# untitled.net
KiCad netlist of a schematic drawn in EAGLE
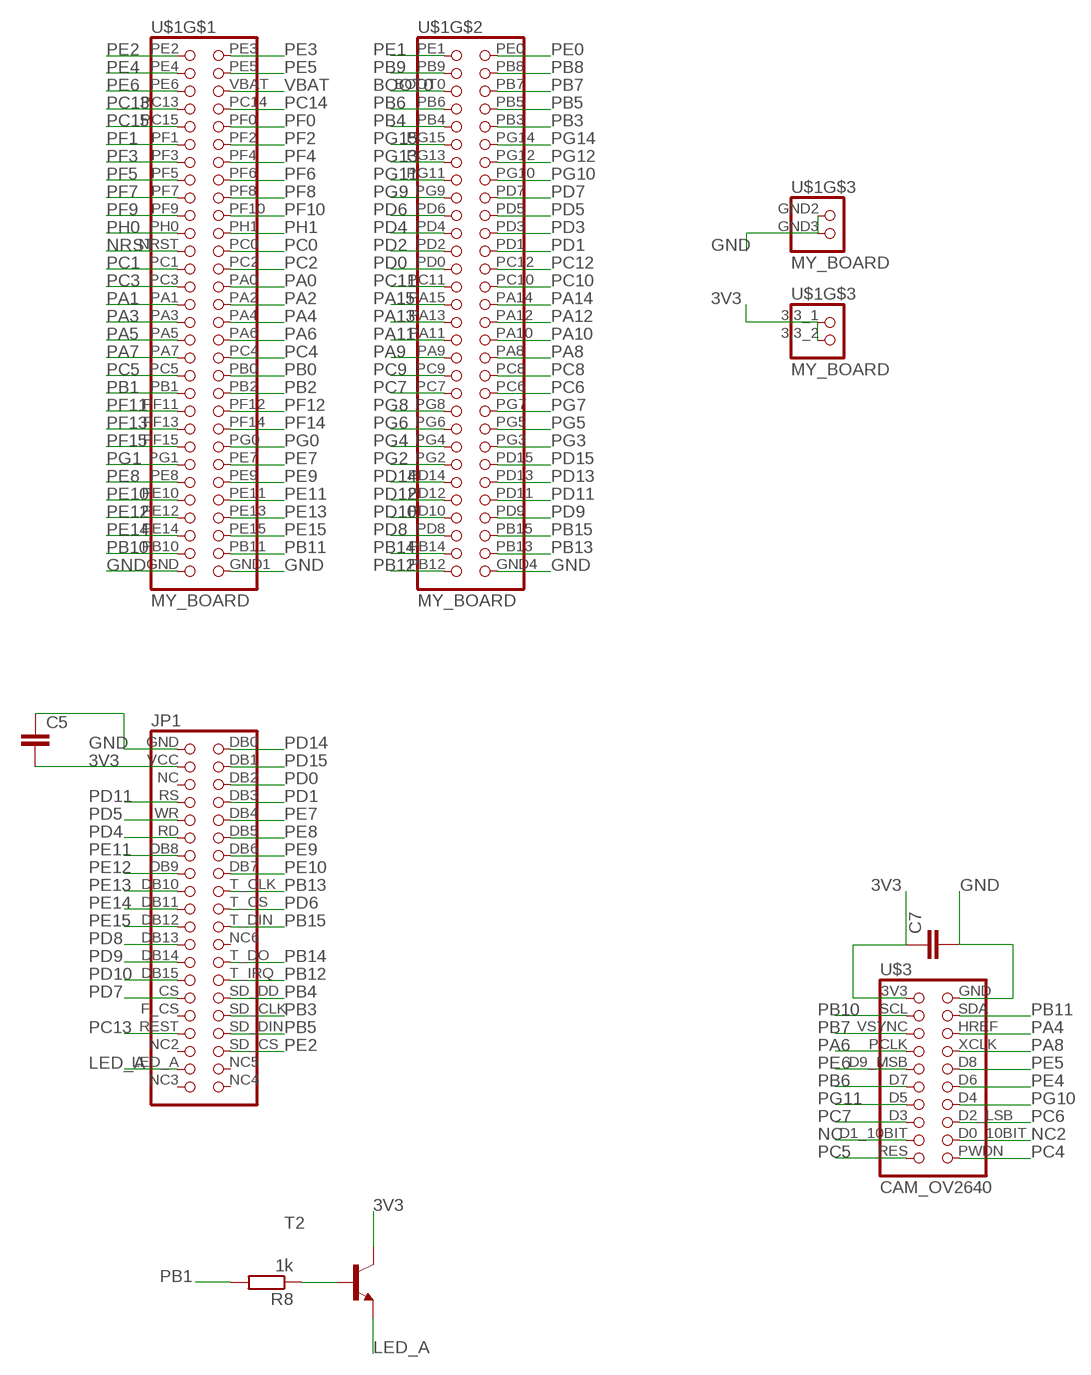
[diagram p0: schematic, sheet 1]

(export (version "E")
  (design (tool "Eeschema 10.0.6"))
  (components
    (comp (ref "C5")
      (value "C-EUC1206")
      (footprint "eagle-import:C1206")
      (libsource (lib "eagle-import") (part "C-EUC1206"))
    )
    (comp (ref "C7")
      (value "C-EUC1206")
      (footprint "eagle-import:C1206")
      (libsource (lib "eagle-import") (part "C-EUC1206"))
    )
    (comp (ref "JP1")
      (value "LCD320QVBLCD320QVB")
      (footprint "eagle-import:2X20")
      (libsource (lib "eagle-import") (part "LCD320QVBLCD320QVB"))
    )
    (comp (ref "R8")
      (value "1k")
      (footprint "eagle-import:R1206")
      (libsource (lib "eagle-import") (part "R-EU_R1206"))
    )
    (comp (ref "T2")
      (value "BC817-16-NPN-SOT23-BEC")
      (footprint "eagle-import:SOT23-BEC")
      (libsource (lib "eagle-import") (part "-NPN-SOT23-BECBC817-16"))
    )
    (comp (ref "U$1")
      (value "MY_BOARD")
      (footprint "eagle-import:MY_BOARD")
      (libsource (lib "eagle-import") (part "MY_BOARD"))
    )
    (comp (ref "U$3")
      (value "CAM_OV2640")
      (footprint "eagle-import:CAM_OV2640")
      (libsource (lib "eagle-import") (part "CAM_OV2640"))
    )
  )
  (nets
    (net (code "1") (name "/3V3") (class "Default")
      (node (ref "C5") (pin "2") (pinfunction "2_2") (pintype "passive"))
      (node (ref "C7") (pin "1") (pinfunction "1_1") (pintype "passive"))
      (node (ref "JP1") (pin "VCC") (pinfunction "3_VCC") (pintype "passive"))
      (node (ref "T2") (pin "C") (pinfunction "C_C") (pintype "passive"))
      (node (ref "U$1") (pin "3,3_1") (pinfunction "1_3,3_1") (pintype "passive"))
      (node (ref "U$1") (pin "3,3_2") (pinfunction "2_3,3_2") (pintype "passive"))
      (node (ref "U$3") (pin "3V3") (pinfunction "3V3_3V3") (pintype "passive"))
    )
    (net (code "2") (name "/BOOT0") (class "Default")
      (node (ref "U$1") (pin "BOOT0") (pinfunction "5_BOOT0") (pintype "passive"))
    )
    (net (code "3") (name "/GND") (class "Default")
      (node (ref "C5") (pin "1") (pinfunction "1_1") (pintype "passive"))
      (node (ref "C7") (pin "2") (pinfunction "2_2") (pintype "passive"))
      (node (ref "JP1") (pin "GND") (pinfunction "1_GND") (pintype "passive"))
      (node (ref "U$1") (pin "GND") (pinfunction "59_GND") (pintype "passive"))
      (node (ref "U$1") (pin "GND1") (pinfunction "60_GND1") (pintype "passive"))
      (node (ref "U$1") (pin "GND2") (pinfunction "3_GND2") (pintype "passive"))
      (node (ref "U$1") (pin "GND3") (pinfunction "4_GND3") (pintype "passive"))
      (node (ref "U$1") (pin "GND4") (pinfunction "60_GND4") (pintype "passive"))
      (node (ref "U$3") (pin "GND") (pinfunction "GND_GND") (pintype "passive"))
    )
    (net (code "4") (name "/LED_A") (class "Default")
      (node (ref "JP1") (pin "LED_A") (pinfunction "37_LED_A") (pintype "passive"))
      (node (ref "T2") (pin "E") (pinfunction "E_E") (pintype "passive"))
    )
    (net (code "5") (name "/NC") (class "Default")
      (node (ref "U$3") (pin "D1_10BIT") (pinfunction "D1_10BIT_D1_10BIT") (pintype "passive"))
    )
    (net (code "6") (name "/NC2") (class "Default")
      (node (ref "U$3") (pin "D0_10BIT") (pinfunction "D0_10BIT_D0_10BIT") (pintype "passive"))
    )
    (net (code "7") (name "/NRST") (class "Default")
      (node (ref "U$1") (pin "NRST") (pinfunction "23_NRST") (pintype "passive"))
    )
    (net (code "8") (name "/PA0") (class "Default")
      (node (ref "U$1") (pin "PA0") (pinfunction "28_PA0") (pintype "passive"))
    )
    (net (code "9") (name "/PA1") (class "Default")
      (node (ref "U$1") (pin "PA1") (pinfunction "29_PA1") (pintype "passive"))
    )
    (net (code "10") (name "/PA2") (class "Default")
      (node (ref "U$1") (pin "PA2") (pinfunction "30_PA2") (pintype "passive"))
    )
    (net (code "11") (name "/PA3") (class "Default")
      (node (ref "U$1") (pin "PA3") (pinfunction "31_PA3") (pintype "passive"))
    )
    (net (code "12") (name "/PA4") (class "Default")
      (node (ref "U$1") (pin "PA4") (pinfunction "32_PA4") (pintype "passive"))
      (node (ref "U$3") (pin "HREF") (pinfunction "HREF_HREF") (pintype "passive"))
    )
    (net (code "13") (name "/PA5") (class "Default")
      (node (ref "U$1") (pin "PA5") (pinfunction "33_PA5") (pintype "passive"))
    )
    (net (code "14") (name "/PA6") (class "Default")
      (node (ref "U$1") (pin "PA6") (pinfunction "34_PA6") (pintype "passive"))
      (node (ref "U$3") (pin "PCLK") (pinfunction "PCLK_PCLK") (pintype "passive"))
    )
    (net (code "15") (name "/PA7") (class "Default")
      (node (ref "U$1") (pin "PA7") (pinfunction "35_PA7") (pintype "passive"))
    )
    (net (code "16") (name "/PA8") (class "Default")
      (node (ref "U$1") (pin "PA8") (pinfunction "36_PA8") (pintype "passive"))
      (node (ref "U$3") (pin "XCLK") (pinfunction "XCLK_XCLK") (pintype "passive"))
    )
    (net (code "17") (name "/PA9") (class "Default")
      (node (ref "U$1") (pin "PA9") (pinfunction "35_PA9") (pintype "passive"))
    )
    (net (code "18") (name "/PA10") (class "Default")
      (node (ref "U$1") (pin "PA10") (pinfunction "34_PA10") (pintype "passive"))
    )
    (net (code "19") (name "/PA11") (class "Default")
      (node (ref "U$1") (pin "PA11") (pinfunction "33_PA11") (pintype "passive"))
    )
    (net (code "20") (name "/PA12") (class "Default")
      (node (ref "U$1") (pin "PA12") (pinfunction "32_PA12") (pintype "passive"))
    )
    (net (code "21") (name "/PA13") (class "Default")
      (node (ref "U$1") (pin "PA13") (pinfunction "31_PA13") (pintype "passive"))
    )
    (net (code "22") (name "/PA14") (class "Default")
      (node (ref "U$1") (pin "PA14") (pinfunction "30_PA14") (pintype "passive"))
    )
    (net (code "23") (name "/PA15") (class "Default")
      (node (ref "U$1") (pin "PA15") (pinfunction "29_PA15") (pintype "passive"))
    )
    (net (code "24") (name "/PB0") (class "Default")
      (node (ref "U$1") (pin "PB0") (pinfunction "38_PB0") (pintype "passive"))
    )
    (net (code "25") (name "/PB1") (class "Default")
      (node (ref "R8") (pin "2") (pinfunction "2_2") (pintype "passive"))
      (node (ref "U$1") (pin "PB1") (pinfunction "39_PB1") (pintype "passive"))
    )
    (net (code "26") (name "/PB2") (class "Default")
      (node (ref "U$1") (pin "PB2") (pinfunction "40_PB2") (pintype "passive"))
    )
    (net (code "27") (name "/PB3") (class "Default")
      (node (ref "JP1") (pin "SD_CLK") (pinfunction "32_SD_CLK") (pintype "passive"))
      (node (ref "U$1") (pin "PB3") (pinfunction "10_PB3") (pintype "passive"))
    )
    (net (code "28") (name "/PB4") (class "Default")
      (node (ref "JP1") (pin "SD_DD") (pinfunction "30_SD_DD") (pintype "passive"))
      (node (ref "U$1") (pin "PB4") (pinfunction "9_PB4") (pintype "passive"))
    )
    (net (code "29") (name "/PB5") (class "Default")
      (node (ref "JP1") (pin "SD_DIN") (pinfunction "34_SD_DIN") (pintype "passive"))
      (node (ref "U$1") (pin "PB5") (pinfunction "8_PB5") (pintype "passive"))
    )
    (net (code "30") (name "/PB6") (class "Default")
      (node (ref "U$1") (pin "PB6") (pinfunction "7_PB6") (pintype "passive"))
      (node (ref "U$3") (pin "D7") (pinfunction "D7_D7") (pintype "passive"))
    )
    (net (code "31") (name "/PB7") (class "Default")
      (node (ref "U$1") (pin "PB7") (pinfunction "6_PB7") (pintype "passive"))
      (node (ref "U$3") (pin "VSYNC") (pinfunction "VSYNC_VSYNC") (pintype "passive"))
    )
    (net (code "32") (name "/PB8") (class "Default")
      (node (ref "U$1") (pin "PB8") (pinfunction "4_PB8") (pintype "passive"))
    )
    (net (code "33") (name "/PB9") (class "Default")
      (node (ref "U$1") (pin "PB9") (pinfunction "3_PB9") (pintype "passive"))
    )
    (net (code "34") (name "/PB10") (class "Default")
      (node (ref "U$1") (pin "PB10") (pinfunction "57_PB10") (pintype "passive"))
      (node (ref "U$3") (pin "SCL") (pinfunction "SCL_SCL") (pintype "passive"))
    )
    (net (code "35") (name "/PB11") (class "Default")
      (node (ref "U$1") (pin "PB11") (pinfunction "58_PB11") (pintype "passive"))
      (node (ref "U$3") (pin "SDA") (pinfunction "SDA_SDA") (pintype "passive"))
    )
    (net (code "36") (name "/PB12") (class "Default")
      (node (ref "JP1") (pin "T_IRQ") (pinfunction "28_T_IRQ") (pintype "passive"))
      (node (ref "U$1") (pin "PB12") (pinfunction "59_PB12") (pintype "passive"))
    )
    (net (code "37") (name "/PB13") (class "Default")
      (node (ref "JP1") (pin "T_CLK") (pinfunction "18_T_CLK") (pintype "passive"))
      (node (ref "U$1") (pin "PB13") (pinfunction "58_PB13") (pintype "passive"))
    )
    (net (code "38") (name "/PB14") (class "Default")
      (node (ref "JP1") (pin "T_DO") (pinfunction "26_T_DO") (pintype "passive"))
      (node (ref "U$1") (pin "PB14") (pinfunction "57_PB14") (pintype "passive"))
    )
    (net (code "39") (name "/PB15") (class "Default")
      (node (ref "JP1") (pin "T_DIN") (pinfunction "22_T_DIN") (pintype "passive"))
      (node (ref "U$1") (pin "PB15") (pinfunction "56_PB15") (pintype "passive"))
    )
    (net (code "40") (name "/PC0") (class "Default")
      (node (ref "U$1") (pin "PC0") (pinfunction "24_PC0") (pintype "passive"))
    )
    (net (code "41") (name "/PC1") (class "Default")
      (node (ref "U$1") (pin "PC1") (pinfunction "25_PC1") (pintype "passive"))
    )
    (net (code "42") (name "/PC2") (class "Default")
      (node (ref "U$1") (pin "PC2") (pinfunction "26_PC2") (pintype "passive"))
    )
    (net (code "43") (name "/PC3") (class "Default")
      (node (ref "U$1") (pin "PC3") (pinfunction "27_PC3") (pintype "passive"))
    )
    (net (code "44") (name "/PC4") (class "Default")
      (node (ref "U$1") (pin "PC4") (pinfunction "36_PC4") (pintype "passive"))
      (node (ref "U$3") (pin "PWDN") (pinfunction "PWDN_PWDN") (pintype "passive"))
    )
    (net (code "45") (name "/PC5") (class "Default")
      (node (ref "U$1") (pin "PC5") (pinfunction "37_PC5") (pintype "passive"))
      (node (ref "U$3") (pin "RES") (pinfunction "RES_RES") (pintype "passive"))
    )
    (net (code "46") (name "/PC6") (class "Default")
      (node (ref "U$1") (pin "PC6") (pinfunction "40_PC6") (pintype "passive"))
      (node (ref "U$3") (pin "D2_LSB") (pinfunction "D2_LSB_D2_LSB") (pintype "passive"))
    )
    (net (code "47") (name "/PC7") (class "Default")
      (node (ref "U$1") (pin "PC7") (pinfunction "39_PC7") (pintype "passive"))
      (node (ref "U$3") (pin "D3") (pinfunction "D3_D3") (pintype "passive"))
    )
    (net (code "48") (name "/PC8") (class "Default")
      (node (ref "U$1") (pin "PC8") (pinfunction "38_PC8") (pintype "passive"))
    )
    (net (code "49") (name "/PC9") (class "Default")
      (node (ref "U$1") (pin "PC9") (pinfunction "37_PC9") (pintype "passive"))
    )
    (net (code "50") (name "/PC10") (class "Default")
      (node (ref "U$1") (pin "PC10") (pinfunction "28_PC10") (pintype "passive"))
    )
    (net (code "51") (name "/PC11") (class "Default")
      (node (ref "U$1") (pin "PC11") (pinfunction "27_PC11") (pintype "passive"))
    )
    (net (code "52") (name "/PC12") (class "Default")
      (node (ref "U$1") (pin "PC12") (pinfunction "26_PC12") (pintype "passive"))
    )
    (net (code "53") (name "/PC13") (class "Default")
      (node (ref "JP1") (pin "REST") (pinfunction "33_REST") (pintype "passive"))
      (node (ref "U$1") (pin "PC13") (pinfunction "7_PC13") (pintype "passive"))
    )
    (net (code "54") (name "/PC14") (class "Default")
      (node (ref "U$1") (pin "PC14") (pinfunction "8_PC14") (pintype "passive"))
    )
    (net (code "55") (name "/PC15") (class "Default")
      (node (ref "U$1") (pin "PC15") (pinfunction "9_PC15") (pintype "passive"))
    )
    (net (code "56") (name "/PD0") (class "Default")
      (node (ref "JP1") (pin "DB2") (pinfunction "6_DB2") (pintype "passive"))
      (node (ref "U$1") (pin "PD0") (pinfunction "25_PD0") (pintype "passive"))
    )
    (net (code "57") (name "/PD1") (class "Default")
      (node (ref "JP1") (pin "DB3") (pinfunction "8_DB3") (pintype "passive"))
      (node (ref "U$1") (pin "PD1") (pinfunction "24_PD1") (pintype "passive"))
    )
    (net (code "58") (name "/PD2") (class "Default")
      (node (ref "U$1") (pin "PD2") (pinfunction "23_PD2") (pintype "passive"))
    )
    (net (code "59") (name "/PD3") (class "Default")
      (node (ref "U$1") (pin "PD3") (pinfunction "22_PD3") (pintype "passive"))
    )
    (net (code "60") (name "/PD4") (class "Default")
      (node (ref "JP1") (pin "RD") (pinfunction "11_RD") (pintype "passive"))
      (node (ref "U$1") (pin "PD4") (pinfunction "21_PD4") (pintype "passive"))
    )
    (net (code "61") (name "/PD5") (class "Default")
      (node (ref "JP1") (pin "WR") (pinfunction "9_WR") (pintype "passive"))
      (node (ref "U$1") (pin "PD5") (pinfunction "20_PD5") (pintype "passive"))
    )
    (net (code "62") (name "/PD6") (class "Default")
      (node (ref "JP1") (pin "T_CS") (pinfunction "20_T_CS") (pintype "passive"))
      (node (ref "U$1") (pin "PD6") (pinfunction "19_PD6") (pintype "passive"))
    )
    (net (code "63") (name "/PD7") (class "Default")
      (node (ref "JP1") (pin "CS") (pinfunction "29_CS") (pintype "passive"))
      (node (ref "U$1") (pin "PD7") (pinfunction "18_PD7") (pintype "passive"))
    )
    (net (code "64") (name "/PD8") (class "Default")
      (node (ref "JP1") (pin "DB13") (pinfunction "23_DB13") (pintype "passive"))
      (node (ref "U$1") (pin "PD8") (pinfunction "55_PD8") (pintype "passive"))
    )
    (net (code "65") (name "/PD9") (class "Default")
      (node (ref "JP1") (pin "DB14") (pinfunction "25_DB14") (pintype "passive"))
      (node (ref "U$1") (pin "PD9") (pinfunction "54_PD9") (pintype "passive"))
    )
    (net (code "66") (name "/PD10") (class "Default")
      (node (ref "JP1") (pin "DB15") (pinfunction "27_DB15") (pintype "passive"))
      (node (ref "U$1") (pin "PD10") (pinfunction "53_PD10") (pintype "passive"))
    )
    (net (code "67") (name "/PD11") (class "Default")
      (node (ref "JP1") (pin "RS") (pinfunction "7_RS") (pintype "passive"))
      (node (ref "U$1") (pin "PD11") (pinfunction "52_PD11") (pintype "passive"))
    )
    (net (code "68") (name "/PD12") (class "Default")
      (node (ref "U$1") (pin "PD12") (pinfunction "51_PD12") (pintype "passive"))
    )
    (net (code "69") (name "/PD13") (class "Default")
      (node (ref "U$1") (pin "PD13") (pinfunction "50_PD13") (pintype "passive"))
    )
    (net (code "70") (name "/PD14") (class "Default")
      (node (ref "JP1") (pin "DB0") (pinfunction "2_DB0") (pintype "passive"))
      (node (ref "U$1") (pin "PD14") (pinfunction "49_PD14") (pintype "passive"))
    )
    (net (code "71") (name "/PD15") (class "Default")
      (node (ref "JP1") (pin "DB1") (pinfunction "4_DB1") (pintype "passive"))
      (node (ref "U$1") (pin "PD15") (pinfunction "48_PD15") (pintype "passive"))
    )
    (net (code "72") (name "/PE0") (class "Default")
      (node (ref "U$1") (pin "PE0") (pinfunction "2_PE0") (pintype "passive"))
    )
    (net (code "73") (name "/PE1") (class "Default")
      (node (ref "U$1") (pin "PE1") (pinfunction "1_PE1") (pintype "passive"))
    )
    (net (code "74") (name "/PE2") (class "Default")
      (node (ref "JP1") (pin "SD_CS") (pinfunction "36_SD_CS") (pintype "passive"))
      (node (ref "U$1") (pin "PE2") (pinfunction "1_PE2") (pintype "passive"))
    )
    (net (code "75") (name "/PE3") (class "Default")
      (node (ref "U$1") (pin "PE3") (pinfunction "2_PE3") (pintype "passive"))
    )
    (net (code "76") (name "/PE4") (class "Default")
      (node (ref "U$1") (pin "PE4") (pinfunction "3_PE4") (pintype "passive"))
      (node (ref "U$3") (pin "D6") (pinfunction "D6_D6") (pintype "passive"))
    )
    (net (code "77") (name "/PE5") (class "Default")
      (node (ref "U$1") (pin "PE5") (pinfunction "4_PE5") (pintype "passive"))
      (node (ref "U$3") (pin "D8") (pinfunction "D8_D8") (pintype "passive"))
    )
    (net (code "78") (name "/PE6") (class "Default")
      (node (ref "U$1") (pin "PE6") (pinfunction "5_PE6") (pintype "passive"))
      (node (ref "U$3") (pin "D9_MSB") (pinfunction "D9_MSB_D9_MSB") (pintype "passive"))
    )
    (net (code "79") (name "/PE7") (class "Default")
      (node (ref "JP1") (pin "DB4") (pinfunction "10_DB4") (pintype "passive"))
      (node (ref "U$1") (pin "PE7") (pinfunction "48_PE7") (pintype "passive"))
    )
    (net (code "80") (name "/PE8") (class "Default")
      (node (ref "JP1") (pin "DB5") (pinfunction "12_DB5") (pintype "passive"))
      (node (ref "U$1") (pin "PE8") (pinfunction "49_PE8") (pintype "passive"))
    )
    (net (code "81") (name "/PE9") (class "Default")
      (node (ref "JP1") (pin "DB6") (pinfunction "14_DB6") (pintype "passive"))
      (node (ref "U$1") (pin "PE9") (pinfunction "50_PE9") (pintype "passive"))
    )
    (net (code "82") (name "/PE10") (class "Default")
      (node (ref "JP1") (pin "DB7") (pinfunction "16_DB7") (pintype "passive"))
      (node (ref "U$1") (pin "PE10") (pinfunction "51_PE10") (pintype "passive"))
    )
    (net (code "83") (name "/PE11") (class "Default")
      (node (ref "JP1") (pin "DB8") (pinfunction "13_DB8") (pintype "passive"))
      (node (ref "U$1") (pin "PE11") (pinfunction "52_PE11") (pintype "passive"))
    )
    (net (code "84") (name "/PE12") (class "Default")
      (node (ref "JP1") (pin "DB9") (pinfunction "15_DB9") (pintype "passive"))
      (node (ref "U$1") (pin "PE12") (pinfunction "53_PE12") (pintype "passive"))
    )
    (net (code "85") (name "/PE13") (class "Default")
      (node (ref "JP1") (pin "DB10") (pinfunction "17_DB10") (pintype "passive"))
      (node (ref "U$1") (pin "PE13") (pinfunction "54_PE13") (pintype "passive"))
    )
    (net (code "86") (name "/PE14") (class "Default")
      (node (ref "JP1") (pin "DB11") (pinfunction "19_DB11") (pintype "passive"))
      (node (ref "U$1") (pin "PE14") (pinfunction "55_PE14") (pintype "passive"))
    )
    (net (code "87") (name "/PE15") (class "Default")
      (node (ref "JP1") (pin "DB12") (pinfunction "21_DB12") (pintype "passive"))
      (node (ref "U$1") (pin "PE15") (pinfunction "56_PE15") (pintype "passive"))
    )
    (net (code "88") (name "/PF0") (class "Default")
      (node (ref "U$1") (pin "PF0") (pinfunction "10_PF0") (pintype "passive"))
    )
    (net (code "89") (name "/PF1") (class "Default")
      (node (ref "U$1") (pin "PF1") (pinfunction "11_PF1") (pintype "passive"))
    )
    (net (code "90") (name "/PF2") (class "Default")
      (node (ref "U$1") (pin "PF2") (pinfunction "12_PF2") (pintype "passive"))
    )
    (net (code "91") (name "/PF3") (class "Default")
      (node (ref "U$1") (pin "PF3") (pinfunction "13_PF3") (pintype "passive"))
    )
    (net (code "92") (name "/PF4") (class "Default")
      (node (ref "U$1") (pin "PF4") (pinfunction "14_PF4") (pintype "passive"))
    )
    (net (code "93") (name "/PF5") (class "Default")
      (node (ref "U$1") (pin "PF5") (pinfunction "15_PF5") (pintype "passive"))
    )
    (net (code "94") (name "/PF6") (class "Default")
      (node (ref "U$1") (pin "PF6") (pinfunction "16_PF6") (pintype "passive"))
    )
    (net (code "95") (name "/PF7") (class "Default")
      (node (ref "U$1") (pin "PF7") (pinfunction "17_PF7") (pintype "passive"))
    )
    (net (code "96") (name "/PF8") (class "Default")
      (node (ref "U$1") (pin "PF8") (pinfunction "18_PF8") (pintype "passive"))
    )
    (net (code "97") (name "/PF9") (class "Default")
      (node (ref "U$1") (pin "PF9") (pinfunction "19_PF9") (pintype "passive"))
    )
    (net (code "98") (name "/PF10") (class "Default")
      (node (ref "U$1") (pin "PF10") (pinfunction "20_PF10") (pintype "passive"))
    )
    (net (code "99") (name "/PF11") (class "Default")
      (node (ref "U$1") (pin "PF11") (pinfunction "41_PF11") (pintype "passive"))
    )
    (net (code "100") (name "/PF12") (class "Default")
      (node (ref "U$1") (pin "PF12") (pinfunction "42_PF12") (pintype "passive"))
    )
    (net (code "101") (name "/PF13") (class "Default")
      (node (ref "U$1") (pin "PF13") (pinfunction "43_PF13") (pintype "passive"))
    )
    (net (code "102") (name "/PF14") (class "Default")
      (node (ref "U$1") (pin "PF14") (pinfunction "44_PF14") (pintype "passive"))
    )
    (net (code "103") (name "/PF15") (class "Default")
      (node (ref "U$1") (pin "PF15") (pinfunction "45_PF15") (pintype "passive"))
    )
    (net (code "104") (name "/PG0") (class "Default")
      (node (ref "U$1") (pin "PG0") (pinfunction "46_PG0") (pintype "passive"))
    )
    (net (code "105") (name "/PG1") (class "Default")
      (node (ref "U$1") (pin "PG1") (pinfunction "47_PG1") (pintype "passive"))
    )
    (net (code "106") (name "/PG2") (class "Default")
      (node (ref "U$1") (pin "PG2") (pinfunction "47_PG2") (pintype "passive"))
    )
    (net (code "107") (name "/PG3") (class "Default")
      (node (ref "U$1") (pin "PG3") (pinfunction "46_PG3") (pintype "passive"))
    )
    (net (code "108") (name "/PG4") (class "Default")
      (node (ref "U$1") (pin "PG4") (pinfunction "45_PG4") (pintype "passive"))
    )
    (net (code "109") (name "/PG5") (class "Default")
      (node (ref "U$1") (pin "PG5") (pinfunction "44_PG5") (pintype "passive"))
    )
    (net (code "110") (name "/PG6") (class "Default")
      (node (ref "U$1") (pin "PG6") (pinfunction "43_PG6") (pintype "passive"))
    )
    (net (code "111") (name "/PG7") (class "Default")
      (node (ref "U$1") (pin "PG7") (pinfunction "42_PG7") (pintype "passive"))
    )
    (net (code "112") (name "/PG8") (class "Default")
      (node (ref "U$1") (pin "PG8") (pinfunction "41_PG8") (pintype "passive"))
    )
    (net (code "113") (name "/PG9") (class "Default")
      (node (ref "U$1") (pin "PG9") (pinfunction "17_PG9") (pintype "passive"))
    )
    (net (code "114") (name "/PG10") (class "Default")
      (node (ref "U$1") (pin "PG10") (pinfunction "16_PG10") (pintype "passive"))
      (node (ref "U$3") (pin "D4") (pinfunction "D4_D4") (pintype "passive"))
    )
    (net (code "115") (name "/PG11") (class "Default")
      (node (ref "U$1") (pin "PG11") (pinfunction "15_PG11") (pintype "passive"))
      (node (ref "U$3") (pin "D5") (pinfunction "D5_D5") (pintype "passive"))
    )
    (net (code "116") (name "/PG12") (class "Default")
      (node (ref "U$1") (pin "PG12") (pinfunction "14_PG12") (pintype "passive"))
    )
    (net (code "117") (name "/PG13") (class "Default")
      (node (ref "U$1") (pin "PG13") (pinfunction "13_PG13") (pintype "passive"))
    )
    (net (code "118") (name "/PG14") (class "Default")
      (node (ref "U$1") (pin "PG14") (pinfunction "12_PG14") (pintype "passive"))
    )
    (net (code "119") (name "/PG15") (class "Default")
      (node (ref "U$1") (pin "PG15") (pinfunction "11_PG15") (pintype "passive"))
    )
    (net (code "120") (name "/PH0") (class "Default")
      (node (ref "U$1") (pin "PH0") (pinfunction "21_PH0") (pintype "passive"))
    )
    (net (code "121") (name "/PH1") (class "Default")
      (node (ref "U$1") (pin "PH1") (pinfunction "22_PH1") (pintype "passive"))
    )
    (net (code "122") (name "/VBAT") (class "Default")
      (node (ref "U$1") (pin "VBAT") (pinfunction "6_VBAT") (pintype "passive"))
    )
    (net (code "123") (name "Net-(R8-Pad1)") (class "Default")
      (node (ref "R8") (pin "1") (pinfunction "1_1") (pintype "passive"))
      (node (ref "T2") (pin "B") (pinfunction "B_B") (pintype "passive"))
    )
    (net (code "124") (name "unconnected-(JP1-5-PadNC)") (class "Default")
      (node (ref "JP1") (pin "NC") (pinfunction "5_NC") (pintype "passive"))
    )
    (net (code "125") (name "unconnected-(JP1-24-PadNC6)") (class "Default")
      (node (ref "JP1") (pin "NC6") (pinfunction "24_NC6") (pintype "passive"))
    )
    (net (code "126") (name "unconnected-(JP1-31-PadF_CS)") (class "Default")
      (node (ref "JP1") (pin "F_CS") (pinfunction "31_F_CS") (pintype "passive"))
    )
    (net (code "127") (name "unconnected-(JP1-35-PadNC2)") (class "Default")
      (node (ref "JP1") (pin "NC2") (pinfunction "35_NC2") (pintype "passive"))
    )
    (net (code "128") (name "unconnected-(JP1-38-PadNC5)") (class "Default")
      (node (ref "JP1") (pin "NC5") (pinfunction "38_NC5") (pintype "passive"))
    )
    (net (code "129") (name "unconnected-(JP1-39-PadNC3)") (class "Default")
      (node (ref "JP1") (pin "NC3") (pinfunction "39_NC3") (pintype "passive"))
    )
    (net (code "130") (name "unconnected-(JP1-40-PadNC4)") (class "Default")
      (node (ref "JP1") (pin "NC4") (pinfunction "40_NC4") (pintype "passive"))
    )
  )
)
